# wemos_temp.net
KiCad netlist of a schematic drawn in EAGLE
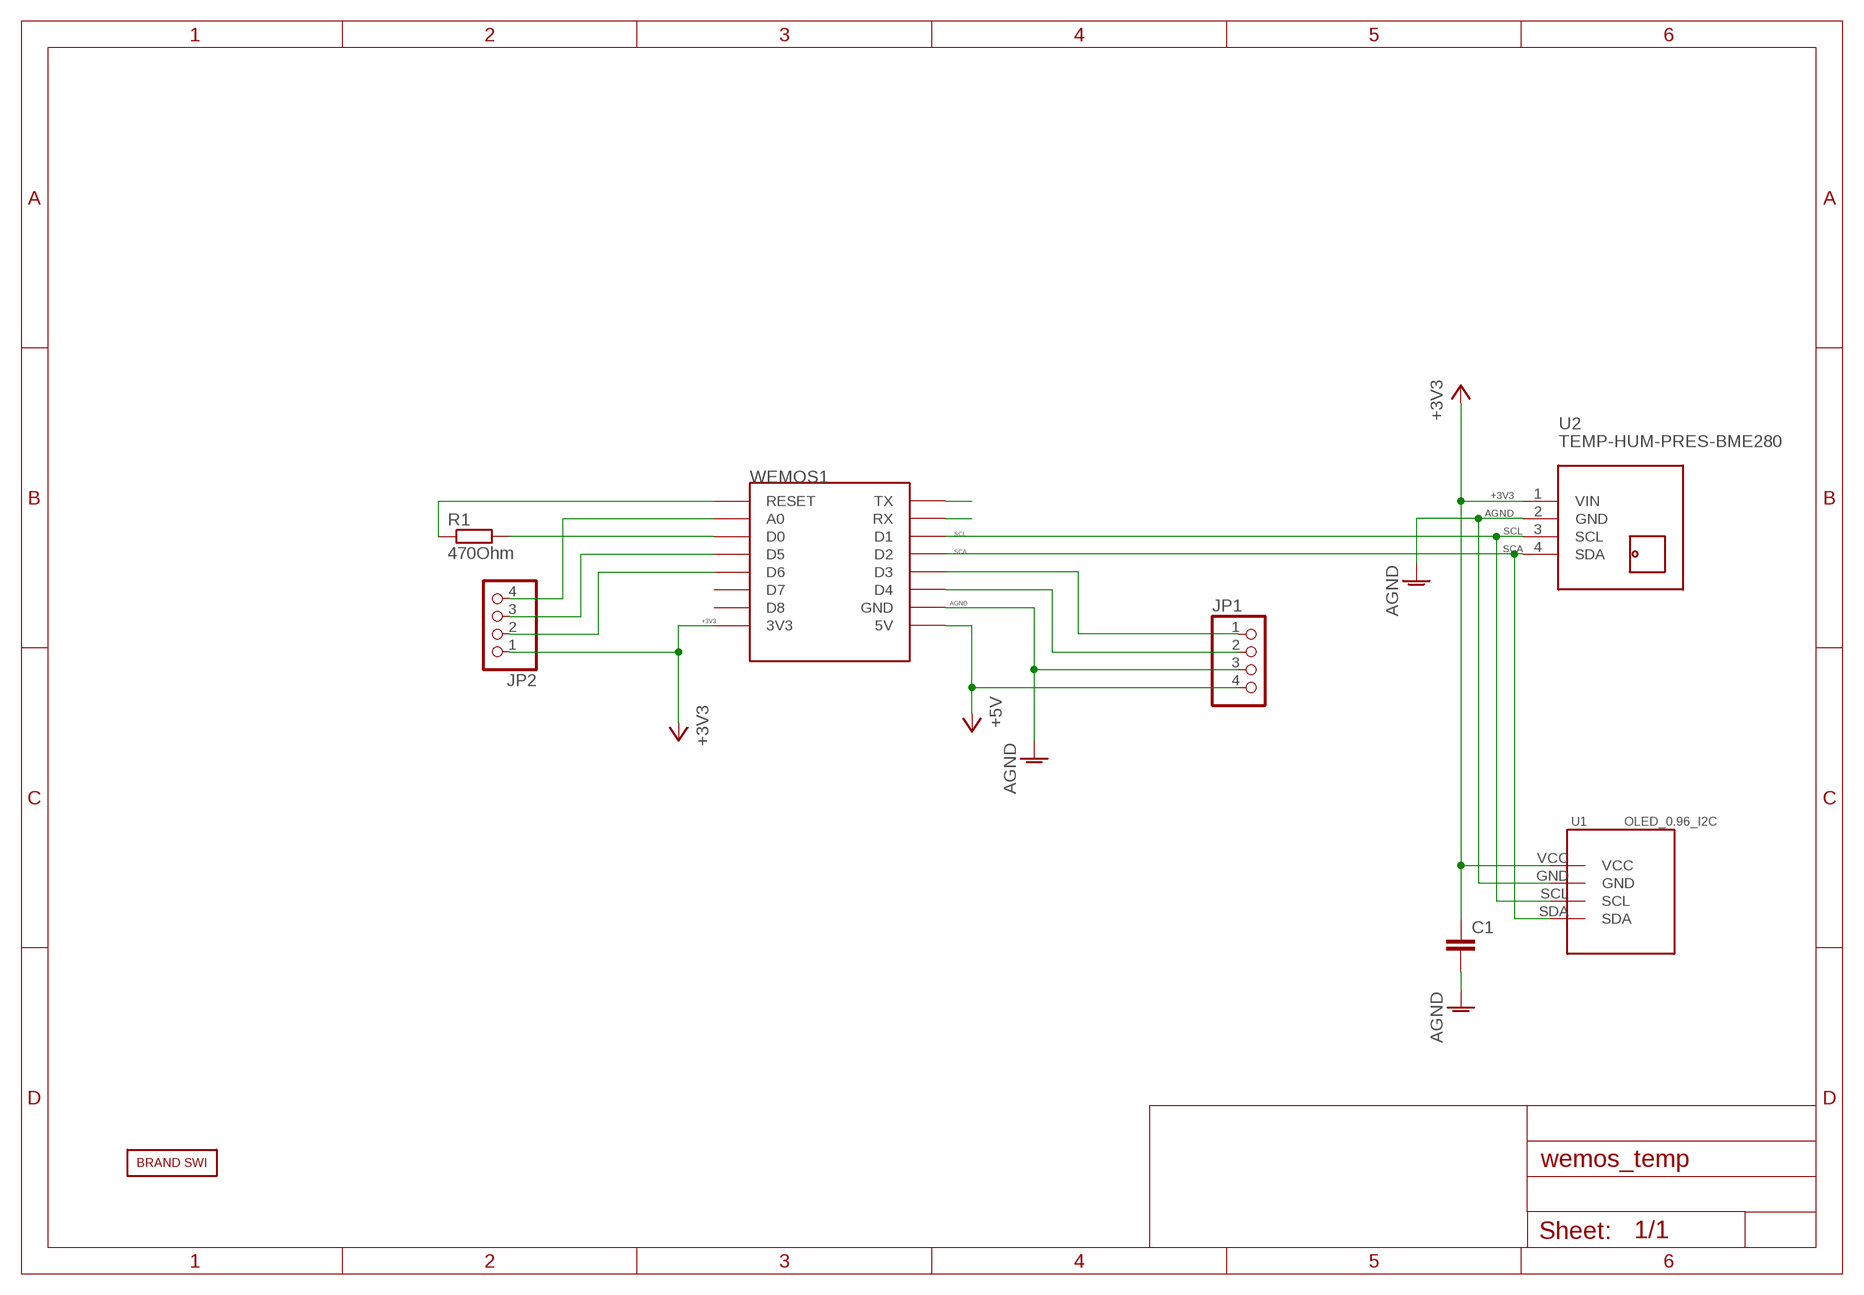
[diagram p0: schematic, sheet 1]

(export (version "E")
  (design (tool "Eeschema 10.0.6"))
  (components
    (comp (ref "C1")
      (value "C-EUC1210")
      (footprint "eagle-import:C1210")
      (libsource (lib "eagle-import") (part "C-EUC1210"))
    )
    (comp (ref "JP1")
      (value "PINHD-1X4")
      (footprint "eagle-import:1X04")
      (libsource (lib "eagle-import") (part "PINHD-1X4"))
    )
    (comp (ref "JP2")
      (value "PINHD-1X4")
      (footprint "eagle-import:1X04")
      (libsource (lib "eagle-import") (part "PINHD-1X4"))
    )
    (comp (ref "R1")
      (value "470Ohm")
      (footprint "eagle-import:R0805")
      (libsource (lib "eagle-import") (part "R-EU_R0805"))
    )
    (comp (ref "U$2")
      (value "BRAND_SWI5X7")
      (footprint "eagle-import:BRAND_SWI_5X7")
      (libsource (lib "eagle-import") (part "BRAND_SWI5X7"))
    )
    (comp (ref "U1")
      (value "OLED_0.96_I2C")
      (footprint "eagle-import:OLED_0.96_I2C")
      (libsource (lib "eagle-import") (part "OLED_0.96_I2C"))
    )
    (comp (ref "U2")
      (value "TEMP-HUM-PRES-BME280")
      (footprint "eagle-import:TEMP-HUM-PRES-BME280")
      (libsource (lib "eagle-import") (part "TEMP-HUM-PRES-BME280"))
    )
    (comp (ref "WEMOS1")
      (value "WEMOS-D1-MINI")
      (footprint "eagle-import:WEMOS-D1-MINI")
      (libsource (lib "eagle-import") (part "WEMOS-D1-MINI"))
    )
  )
  (nets
    (net (code "1") (name "+3V3") (class "Default")
      (node (ref "C1") (pin "1") (pinfunction "1_1") (pintype "passive"))
      (node (ref "JP2") (pin "1") (pinfunction "1_1") (pintype "passive"))
      (node (ref "U1") (pin "VCC") (pinfunction "VCC_VCC") (pintype "bidirectional"))
      (node (ref "U2") (pin "1") (pinfunction "VIN_1") (pintype "power_in"))
      (node (ref "WEMOS1") (pin "3V3") (pinfunction "3V3_3V3") (pintype "bidirectional"))
    )
    (net (code "2") (name "+5V") (class "Default")
      (node (ref "JP1") (pin "4") (pinfunction "4_4") (pintype "passive"))
      (node (ref "WEMOS1") (pin "5V") (pinfunction "5V_5V") (pintype "bidirectional"))
    )
    (net (code "3") (name "/SCA") (class "Default")
      (node (ref "U1") (pin "SDA") (pinfunction "SDA_SDA") (pintype "bidirectional"))
      (node (ref "U2") (pin "4") (pinfunction "SDA_4") (pintype "bidirectional"))
      (node (ref "WEMOS1") (pin "D2") (pinfunction "D2_D2") (pintype "bidirectional"))
    )
    (net (code "4") (name "/SCL") (class "Default")
      (node (ref "U1") (pin "SCL") (pinfunction "SCL_SCL") (pintype "bidirectional"))
      (node (ref "U2") (pin "3") (pinfunction "SCL_3") (pintype "bidirectional"))
      (node (ref "WEMOS1") (pin "D1") (pinfunction "D1_D1") (pintype "bidirectional"))
    )
    (net (code "5") (name "AGND") (class "Default")
      (node (ref "C1") (pin "2") (pinfunction "2_2") (pintype "passive"))
      (node (ref "JP1") (pin "3") (pinfunction "3_3") (pintype "passive"))
      (node (ref "U1") (pin "GND") (pinfunction "GND_GND") (pintype "bidirectional"))
      (node (ref "U2") (pin "2") (pinfunction "GND_2") (pintype "power_in"))
      (node (ref "WEMOS1") (pin "GND") (pinfunction "GND_GND") (pintype "bidirectional"))
    )
    (net (code "6") (name "Net-(JP1-Pad1)") (class "Default")
      (node (ref "JP1") (pin "1") (pinfunction "1_1") (pintype "passive"))
      (node (ref "WEMOS1") (pin "D3") (pinfunction "D3_D3") (pintype "bidirectional"))
    )
    (net (code "7") (name "Net-(JP1-Pad2)") (class "Default")
      (node (ref "JP1") (pin "2") (pinfunction "2_2") (pintype "passive"))
      (node (ref "WEMOS1") (pin "D4") (pinfunction "D4_D4") (pintype "bidirectional"))
    )
    (net (code "8") (name "Net-(JP2-Pad2)") (class "Default")
      (node (ref "JP2") (pin "2") (pinfunction "2_2") (pintype "passive"))
      (node (ref "WEMOS1") (pin "D6") (pinfunction "D6_D6") (pintype "bidirectional"))
    )
    (net (code "9") (name "Net-(JP2-Pad3)") (class "Default")
      (node (ref "JP2") (pin "3") (pinfunction "3_3") (pintype "passive"))
      (node (ref "WEMOS1") (pin "D5") (pinfunction "D5_D5") (pintype "bidirectional"))
    )
    (net (code "10") (name "Net-(JP2-Pad4)") (class "Default")
      (node (ref "JP2") (pin "4") (pinfunction "4_4") (pintype "passive"))
      (node (ref "WEMOS1") (pin "A0") (pinfunction "A0_A0") (pintype "bidirectional"))
    )
    (net (code "11") (name "Net-(R1-Pad1)") (class "Default")
      (node (ref "R1") (pin "1") (pinfunction "1_1") (pintype "passive"))
      (node (ref "WEMOS1") (pin "RESET") (pinfunction "RESET_RESET") (pintype "bidirectional"))
    )
    (net (code "12") (name "Net-(R1-Pad2)") (class "Default")
      (node (ref "R1") (pin "2") (pinfunction "2_2") (pintype "passive"))
      (node (ref "WEMOS1") (pin "D0") (pinfunction "D0_D0") (pintype "bidirectional"))
    )
    (net (code "13") (name "unconnected-(WEMOS1-PadD7)") (class "Default")
      (node (ref "WEMOS1") (pin "D7") (pinfunction "D7_D7") (pintype "bidirectional"))
    )
    (net (code "14") (name "unconnected-(WEMOS1-PadD8)") (class "Default")
      (node (ref "WEMOS1") (pin "D8") (pinfunction "D8_D8") (pintype "bidirectional"))
    )
    (net (code "15") (name "unconnected-(WEMOS1-PadRX)") (class "Default")
      (node (ref "WEMOS1") (pin "RX") (pinfunction "RX_RX") (pintype "bidirectional"))
    )
    (net (code "16") (name "unconnected-(WEMOS1-PadTX)") (class "Default")
      (node (ref "WEMOS1") (pin "TX") (pinfunction "TX_TX") (pintype "bidirectional"))
    )
  )
)
